# wisp-6-main.net
KiCad netlist of a schematic drawn in Altium Designer
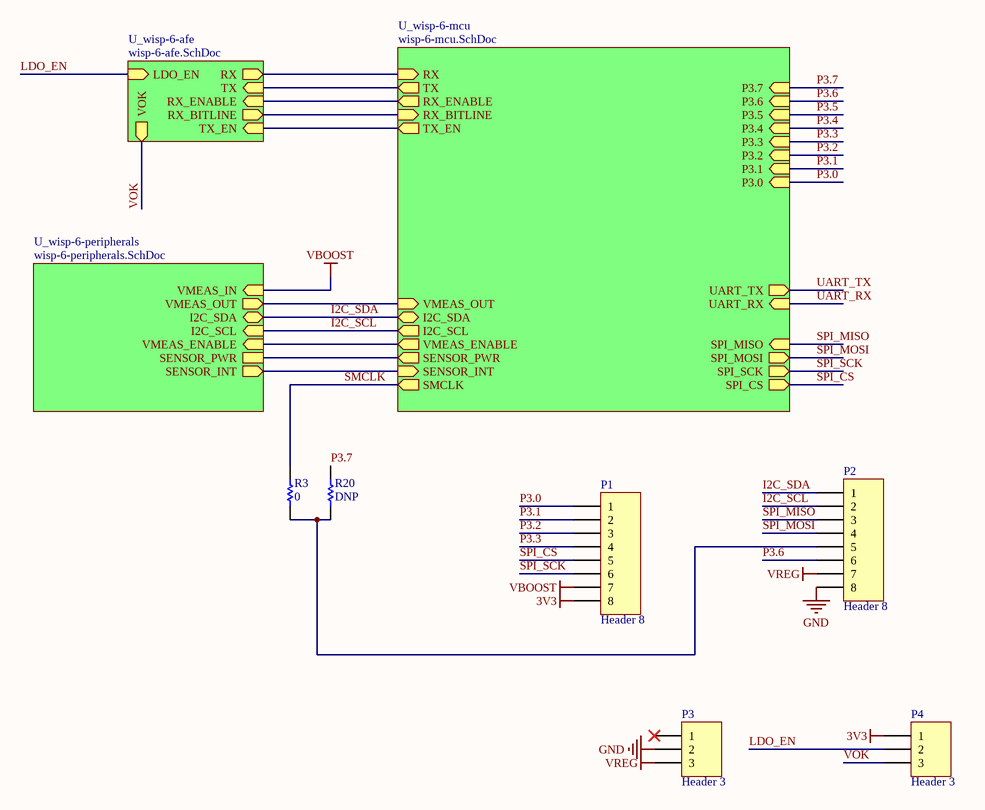
[diagram p0: wisp-6-main.SchDoc]

(export (version "E")
  (design (tool "Eeschema 10.0.6"))
  (components
    (comp (ref "P1")
      (value "Header 8")
      (footprint "HDR1X8")
      (description "Header, 8-Pin")
      (fields (field (name "PUBLISHER") "Altium Limited"))
      (libsource (lib "Miscellaneous Connectors") (part "Header 8"))
    )
    (comp (ref "P2")
      (value "Header 8")
      (footprint "HDR1X8")
      (description "Header, 8-Pin")
      (fields (field (name "PUBLISHER") "Altium Limited"))
      (libsource (lib "Miscellaneous Connectors") (part "Header 8"))
    )
    (comp (ref "P3")
      (value "Header 3")
      (footprint "HDR1X3")
      (description "Header, 3-Pin")
      (fields (field (name "PUBLISHER") "Altium Limited"))
      (libsource (lib "Miscellaneous Connectors") (part "Header 3"))
    )
    (comp (ref "P4")
      (value "Header 3")
      (footprint "HDR1X3")
      (description "Header, 3-Pin")
      (fields (field (name "PUBLISHER") "Altium Limited"))
      (libsource (lib "Miscellaneous Connectors") (part "Header 3"))
    )
    (comp (ref "R3")
      (value "0")
      (footprint "0402")
      (description "Chip Resistor (Surface Mount)")
      (fields (field (name "MANUFACTURER") "Generic Chip Res (TBD)") (field (name "Comment") "Res"))
      (libsource (lib "WISP_AD10") (part "Res"))
    )
    (comp (ref "R20")
      (value "DNP")
      (footprint "0402")
      (description "Chip Resistor (Surface Mount)")
      (fields (field (name "MANUFACTURER") "Generic Chip Res (TBD)") (field (name "Comment") "Res"))
      (libsource (lib "WISP_AD10") (part "Res"))
    )
  )
  (nets
    (net (code "1") (name "/I2C_SCL") (class "Default")
      (node (ref "P2") (pin "2") (pinfunction "2_2") (pintype "passive"))
    )
    (net (code "2") (name "/I2C_SDA") (class "Default")
      (node (ref "P2") (pin "1") (pinfunction "1_1") (pintype "passive"))
    )
    (net (code "3") (name "/LDO_EN") (class "Default")
      (node (ref "P4") (pin "2") (pinfunction "2_2") (pintype "passive"))
    )
    (net (code "4") (name "/P3.0") (class "Default")
      (node (ref "P1") (pin "1") (pinfunction "1_1") (pintype "passive"))
    )
    (net (code "5") (name "/P3.1") (class "Default")
      (node (ref "P1") (pin "2") (pinfunction "2_2") (pintype "passive"))
    )
    (net (code "6") (name "/P3.2") (class "Default")
      (node (ref "P1") (pin "3") (pinfunction "3_3") (pintype "passive"))
    )
    (net (code "7") (name "/P3.3") (class "Default")
      (node (ref "P1") (pin "4") (pinfunction "4_4") (pintype "passive"))
    )
    (net (code "10") (name "/P3.6") (class "Default")
      (node (ref "P2") (pin "6") (pinfunction "6_6") (pintype "passive"))
    )
    (net (code "11") (name "/P3.7") (class "Default")
      (node (ref "R20") (pin "2") (pinfunction "2_2") (pintype "passive"))
    )
    (net (code "17") (name "/SMCLK") (class "Default")
      (node (ref "R3") (pin "2") (pinfunction "2_2") (pintype "passive"))
    )
    (net (code "18") (name "/SPI_CS") (class "Default")
      (node (ref "P1") (pin "5") (pinfunction "5_5") (pintype "passive"))
    )
    (net (code "19") (name "/SPI_MISO") (class "Default")
      (node (ref "P2") (pin "3") (pinfunction "3_3") (pintype "passive"))
    )
    (net (code "20") (name "/SPI_MOSI") (class "Default")
      (node (ref "P2") (pin "4") (pinfunction "4_4") (pintype "passive"))
    )
    (net (code "21") (name "/SPI_SCK") (class "Default")
      (node (ref "P1") (pin "6") (pinfunction "6_6") (pintype "passive"))
    )
    (net (code "28") (name "/VOK") (class "Default")
      (node (ref "P4") (pin "3") (pinfunction "3_3") (pintype "passive"))
    )
    (net (code "29") (name "3V3") (class "Default")
      (node (ref "P1") (pin "8") (pinfunction "8_8") (pintype "passive"))
      (node (ref "P4") (pin "1") (pinfunction "1_1") (pintype "passive"))
    )
    (net (code "30") (name "GND") (class "Default")
      (node (ref "P2") (pin "8") (pinfunction "8_8") (pintype "passive"))
      (node (ref "P3") (pin "2") (pinfunction "2_2") (pintype "passive"))
    )
    (net (code "31") (name "Net-(P2-Pad5)") (class "Default")
      (node (ref "P2") (pin "5") (pinfunction "5_5") (pintype "passive"))
      (node (ref "R20") (pin "1") (pinfunction "1_1") (pintype "passive"))
      (node (ref "R3") (pin "1") (pinfunction "1_1") (pintype "passive"))
    )
    (net (code "32") (name "VBOOST") (class "Default")
      (node (ref "P1") (pin "7") (pinfunction "7_7") (pintype "passive"))
    )
    (net (code "33") (name "VREG") (class "Default")
      (node (ref "P2") (pin "7") (pinfunction "7_7") (pintype "passive"))
      (node (ref "P3") (pin "3") (pinfunction "3_3") (pintype "passive"))
    )
    (net (code "34") (name "unconnected-(P3-Pad1)") (class "Default")
      (node (ref "P3") (pin "1") (pinfunction "1_1") (pintype "passive+no_connect"))
    )
  )
)
